# TEST-MODULE-V2.net
KiCad netlist of a schematic drawn in Altium Designer
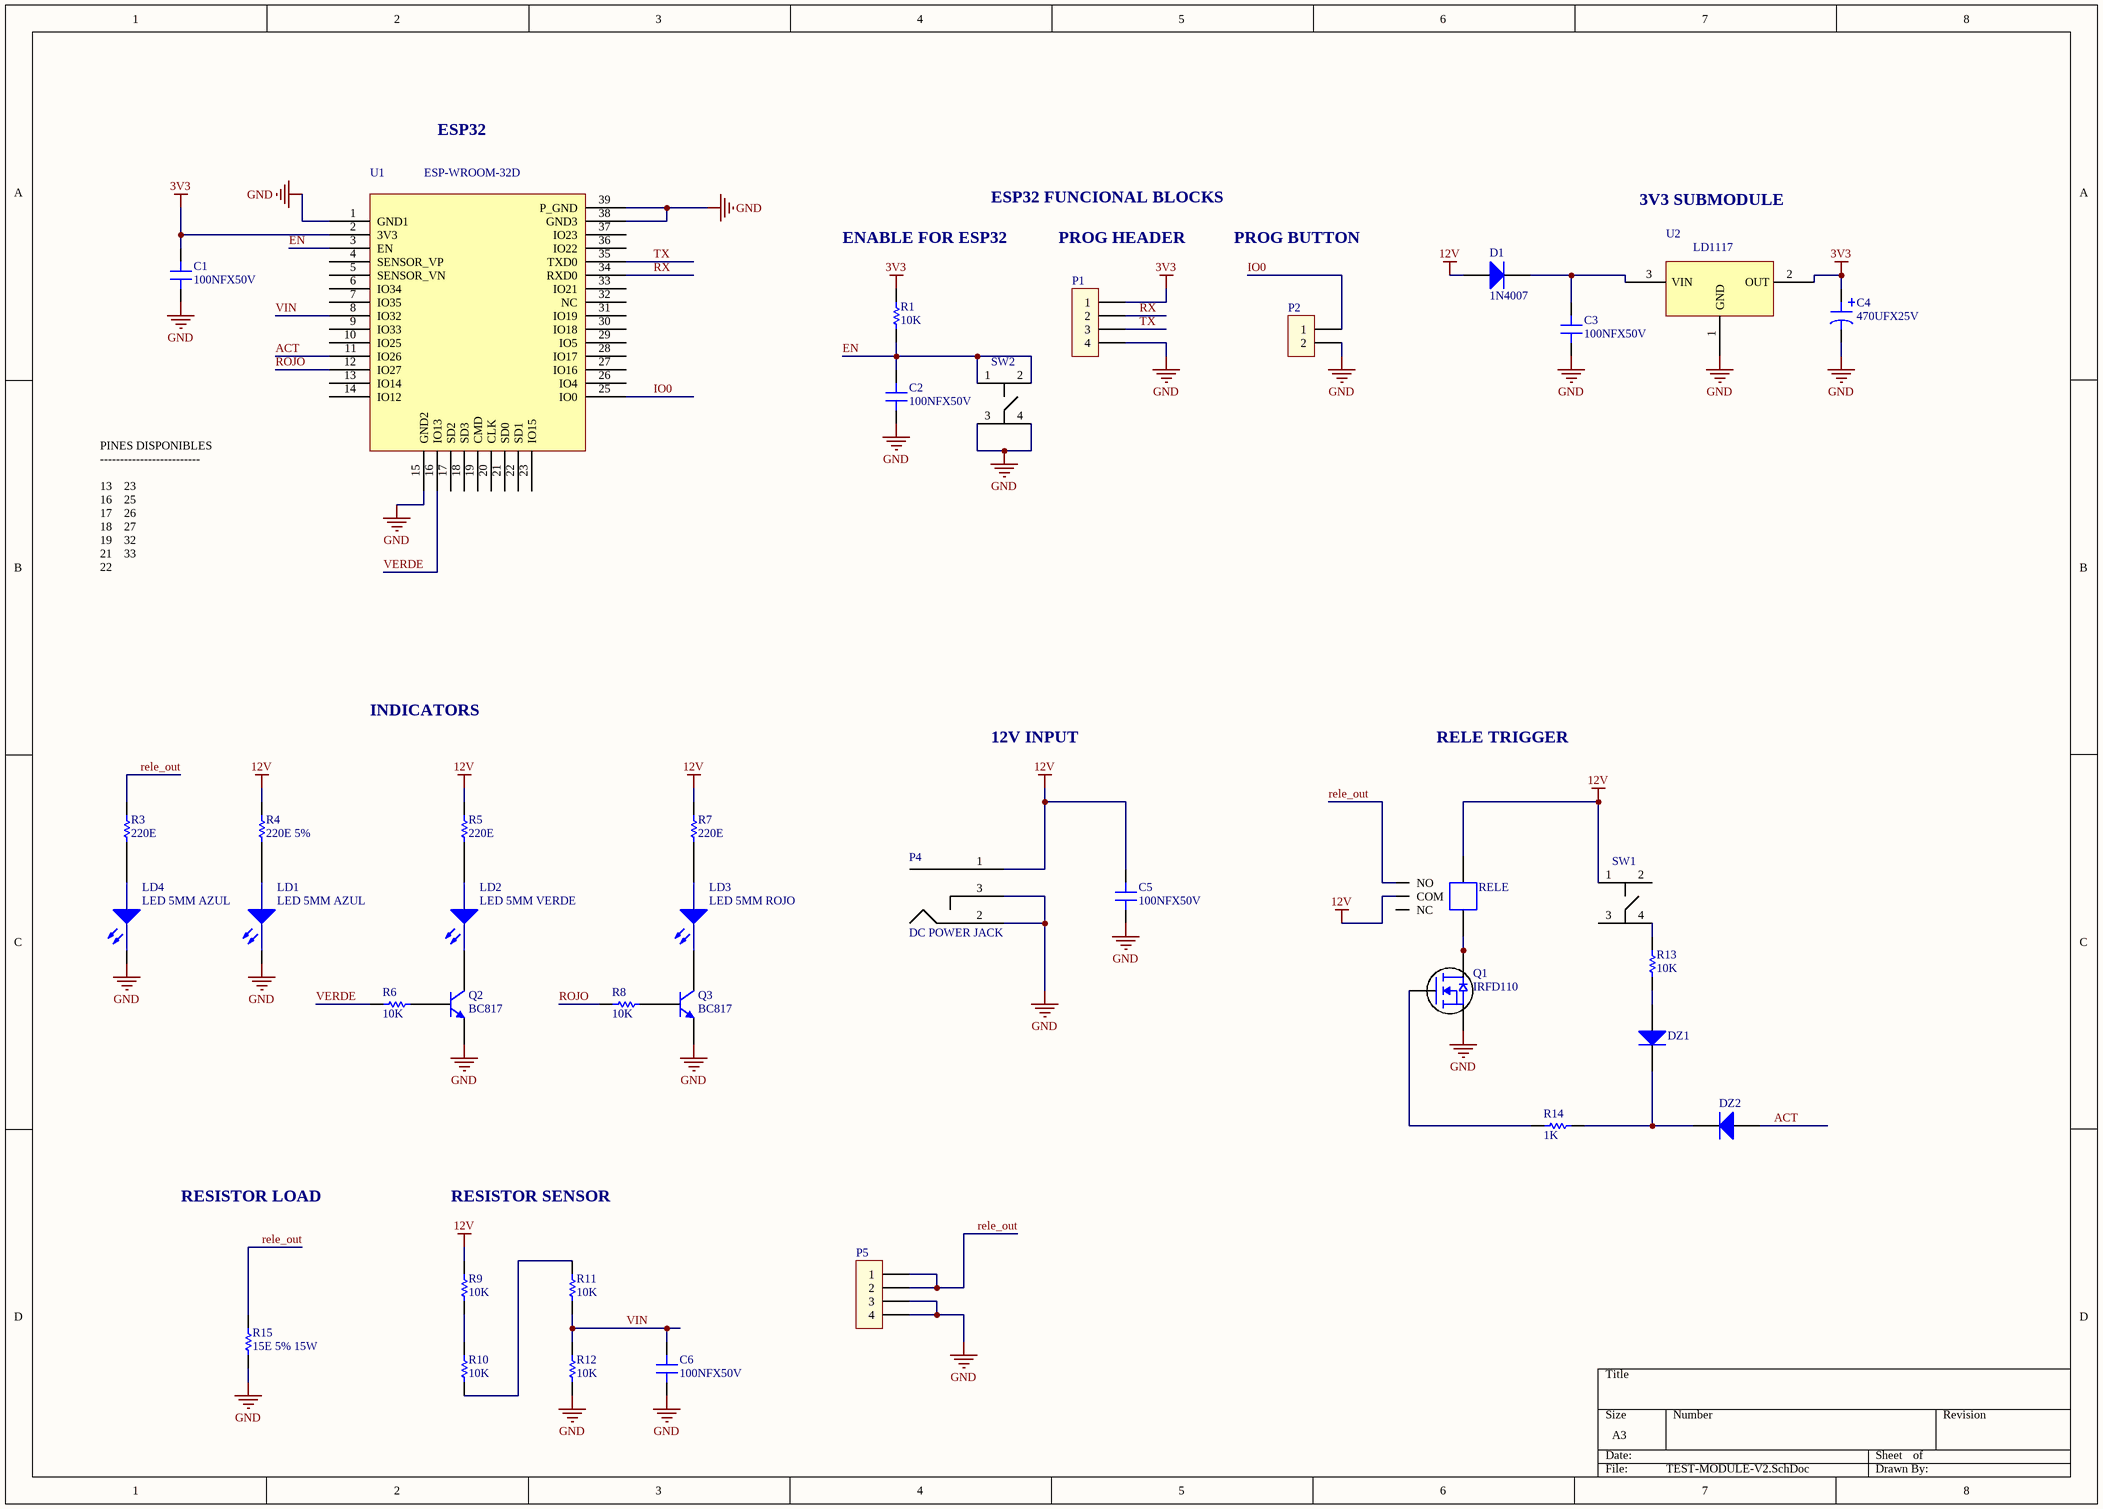
[diagram p0: TEST-MODULE-V2.SchDoc]

(export (version "E")
  (design (tool "Eeschema 10.0.6"))
  (components
    (comp (ref "C1")
      (value "100NFX50V")
      (footprint "CAP.SMD.0805")
      (description "100NFX50V X7R 10% CER.MULT. SMD 0805")
      (libsource (lib "Libreria-Capacitores") (part "Capacitor 100NFX50V X7R 10% CER.MULT. SMD 0805"))
    )
    (comp (ref "C2")
      (value "100NFX50V")
      (footprint "CAP.SMD.0805")
      (description "100NFX50V X7R 10% CER.MULT. SMD 0805")
      (libsource (lib "Libreria-Capacitores") (part "Capacitor 100NFX50V X7R 10% CER.MULT. SMD 0805"))
    )
    (comp (ref "C3")
      (value "100NFX50V")
      (footprint "CAP.SMD.0805")
      (description "100NFX50V X7R 10% CER.MULT. SMD 0805")
      (libsource (lib "Libreria-Capacitores") (part "Capacitor 100NFX50V X7R 10% CER.MULT. SMD 0805"))
    )
    (comp (ref "C4")
      (value "470UFX25V")
      (footprint "CAP-ELEC-10X13")
      (description "470UFX25V 85°C 10x13 ELE.RAD")
      (libsource (lib "Libreria-Capacitores") (part "Capacitor Electrolitico 470UFX25V 85°C 10x13 ELE.RAD"))
    )
    (comp (ref "C5")
      (value "100NFX50V")
      (footprint "CAP.SMD.0805")
      (description "100NFX50V X7R 10% CER.MULT. SMD 0805")
      (libsource (lib "Libreria-Capacitores") (part "Capacitor 100NFX50V X7R 10% CER.MULT. SMD 0805"))
    )
    (comp (ref "C6")
      (value "100NFX50V")
      (footprint "CAP.SMD.0805")
      (description "100NFX50V X7R 10% CER.MULT. SMD 0805")
      (libsource (lib "Libreria-Capacitores") (part "Capacitor 100NFX50V X7R 10% CER.MULT. SMD 0805"))
    )
    (comp (ref "D1")
      (value "1N4007")
      (footprint "Diode DO41")
      (description "Diodo 1N4007 DIODO 1A 1000V DO41")
      (libsource (lib "Libreria-Diodos") (part "Diodo 1N4007 DIODO 1A 1000V DO41"))
    )
    (comp (ref "DZ1")
      (value "M7 DIODO 1A 1000V SMD-SMA (1N4007) XYG")
      (footprint "Diode-SMD-SMA")
      (libsource (lib "Libreria-Diodos") (part "Diodo M7 DIODO 1A 1000V SMD-SMA (1N4007) XYG"))
    )
    (comp (ref "DZ2")
      (value "M7 DIODO 1A 1000V SMD-SMA (1N4007) XYG")
      (footprint "Diode-SMD-SMA")
      (libsource (lib "Libreria-Diodos") (part "Diodo M7 DIODO 1A 1000V SMD-SMA (1N4007) XYG"))
    )
    (comp (ref "LD1")
      (value "LED 5MM AZUL")
      (footprint "LED-5MM-ALTO-9-AZUL")
      (description "LED 5MM AZUL ALTO 9")
      (libsource (lib "Libreria-LEDs") (part "LED 5MM AZUL ALTO 9"))
    )
    (comp (ref "LD2")
      (value "LED 5MM VERDE")
      (footprint "LED-5MM-ALTO-9-VERDE")
      (description "LED 5MM VERDE ALTO 9")
      (libsource (lib "Libreria-LEDs") (part "LED 5MM VERDE ALTO 9"))
    )
    (comp (ref "LD3")
      (value "LED 5MM ROJO")
      (footprint "LED-5MM-ALTO-9-ROJO")
      (description "LED 5MM ROJO ALTO 9")
      (libsource (lib "Libreria-LEDs") (part "LED 5MM ROJO ALTO 9"))
    )
    (comp (ref "LD4")
      (value "LED 5MM AZUL")
      (footprint "LED-5MM-ALTO-9-AZUL")
      (description "LED 5MM AZUL ALTO 9")
      (libsource (lib "Libreria-LEDs") (part "LED 5MM AZUL ALTO 9"))
    )
    (comp (ref "P1")
      (value "IDC-HE-THT-1X4-P2.54MM")
      (footprint "IDC-HE-THT-1X4-P2.54MM")
      (libsource (lib "Libreria-Conectores") (part "IDC-HE-THT-1X4-P2.54MM"))
    )
    (comp (ref "P2")
      (value "IDC-MA-THT-1X2-P2.54MM-L11")
      (footprint "IDC-MA-THT-1X2-P2.54MM-L11")
      (libsource (lib "Libreria-Conectores") (part "IDC-MA-THT-1X2-P2.54MM-L11"))
    )
    (comp (ref "P4")
      (value "DC POWER JACK")
      (footprint "VAR-DC-JACK - VERT")
      (description "DC POWER JACK VERTICAL 2MM")
      (libsource (lib "Libreria-Varios") (part "DC POWER JACK VERTICAL 2MM"))
    )
    (comp (ref "P5")
      (value "IDC-HE-THT-1X4-P2.54MM")
      (footprint "IDC-HE-THT-1X4-P2.54MM")
      (libsource (lib "Libreria-Conectores") (part "IDC-HE-THT-1X4-P2.54MM"))
    )
    (comp (ref "Q1")
      (value "IRFD110")
      (footprint "TRA-IRFD110")
      (description "Transistor MOSFET N IRFD110")
      (libsource (lib "Libreria-Transistores") (part "Transistor MOSFET N IRFD110"))
    )
    (comp (ref "Q2")
      (value "BC817")
      (footprint "NPN.SMD.SOT23")
      (description "BC817-40 TRA.NPN 45V0.5A 0.25W SOT23")
      (libsource (lib "Libreria-Transistores") (part "Transistor BC817-40 TRA.NPN 45V0.5A 0.25W SOT23"))
    )
    (comp (ref "Q3")
      (value "BC817")
      (footprint "NPN.SMD.SOT23")
      (description "BC817-40 TRA.NPN 45V0.5A 0.25W SOT23")
      (libsource (lib "Libreria-Transistores") (part "Transistor BC817-40 TRA.NPN 45V0.5A 0.25W SOT23"))
    )
    (comp (ref "R1")
      (value "10K")
      (footprint "RES.SMD.103")
      (description "10K 5% 0805 1/8W RES.SMD")
      (libsource (lib "Libreria-Resistencias") (part "Resistencia 10K 5% 0805 1/8W"))
    )
    (comp (ref "R3")
      (value "220E")
      (footprint "RES.SMD.221")
      (description "220E 5% 0805 1/8W RES.SMD")
      (libsource (lib "Libreria-Resistencias") (part "Resistencia 220E 5% 0805 1/8W"))
    )
    (comp (ref "R4")
      (value "220E 5%")
      (footprint "RES.SMD.221")
      (description "220E 5% 0805 1/8W RES.SMD")
      (libsource (lib "Libreria-Resistencias") (part "Resistencia 220E 5% 0805 1/8W"))
    )
    (comp (ref "R5")
      (value "220E")
      (footprint "RES.SMD.221")
      (description "220E 5% 0805 1/8W RES.SMD")
      (libsource (lib "Libreria-Resistencias") (part "Resistencia 220E 5% 0805 1/8W"))
    )
    (comp (ref "R6")
      (value "10K")
      (footprint "RES.SMD.103")
      (description "10K 5% 0805 1/8W RES.SMD")
      (libsource (lib "Libreria-Resistencias") (part "Resistencia 10K 5% 0805 1/8W"))
    )
    (comp (ref "R7")
      (value "220E")
      (footprint "RES.SMD.221")
      (description "220E 5% 0805 1/8W RES.SMD")
      (libsource (lib "Libreria-Resistencias") (part "Resistencia 220E 5% 0805 1/8W"))
    )
    (comp (ref "R8")
      (value "10K")
      (footprint "RES.SMD.103")
      (description "10K 5% 0805 1/8W RES.SMD")
      (libsource (lib "Libreria-Resistencias") (part "Resistencia 10K 5% 0805 1/8W"))
    )
    (comp (ref "R9")
      (value "10K")
      (footprint "RES.SMD.103")
      (description "10K 5% 0805 1/8W RES.SMD")
      (libsource (lib "Libreria-Resistencias") (part "Resistencia 10K 5% 0805 1/8W"))
    )
    (comp (ref "R10")
      (value "10K")
      (footprint "RES.SMD.103")
      (description "10K 5% 0805 1/8W RES.SMD")
      (libsource (lib "Libreria-Resistencias") (part "Resistencia 10K 5% 0805 1/8W"))
    )
    (comp (ref "R11")
      (value "10K")
      (footprint "RES.SMD.103")
      (description "10K 5% 0805 1/8W RES.SMD")
      (libsource (lib "Libreria-Resistencias") (part "Resistencia 10K 5% 0805 1/8W"))
    )
    (comp (ref "R12")
      (value "10K")
      (footprint "RES.SMD.103")
      (description "10K 5% 0805 1/8W RES.SMD")
      (libsource (lib "Libreria-Resistencias") (part "Resistencia 10K 5% 0805 1/8W"))
    )
    (comp (ref "R13")
      (value "10K")
      (footprint "RES.SMD.103")
      (description "10K 5% 0805 1/8W RES.SMD")
      (libsource (lib "Libreria-Resistencias") (part "Resistencia 10K 5% 0805 1/8W"))
    )
    (comp (ref "R14")
      (value "1K")
      (footprint "RES.SMD.102")
      (description "1K 5% 0805 1/8W RES.SMD")
      (libsource (lib "Libreria-Resistencias") (part "Resistencia 1K 5% 0805 1/8W"))
    )
    (comp (ref "R15")
      (value "15E 5% 15W")
      (footprint "RES-CERAMICA-15W")
      (description "Resistencia Ceramica 15E 5% 15W SE15 RES.CEM")
      (libsource (lib "Libreria-Resistencias") (part "Resistencia Ceramica 15E 5% 15W SE15 RES.CEM"))
    )
    (comp (ref "RELE")
      (value "Relay simple inversor 5V 10A")
      (footprint "VAR-RELE-5V10A")
      (libsource (lib "Libreria-Varios") (part "VAR-RELE-5V Relay simple inversor 5V 10A"))
    )
    (comp (ref "SW1")
      (value "TACT-SWITCH-THT-4C-06X06(13MM)-JIANFU")
      (footprint "TACT-SWITCH-THT-4C-06X06-13MM")
      (libsource (lib "Libreria-Switches") (part "TACT-SWITCH-THT-4C-06X06(13MM)-JIANFU"))
    )
    (comp (ref "SW2")
      (value "TACT-SWITCH-THT-4C-06X06(5MM)")
      (footprint "TACT-SWITCH-THT-4C-06X06-5MM")
      (libsource (lib "Libreria-Switches") (part "TACT-SWITCH-THT-4C-06X06(5MM)"))
    )
    (comp (ref "U1")
      (value "ESP32-WROOM-32D")
      (footprint "ESP32-WROOM-32D")
      (libsource (lib "Libreria-Semiconductores") (part "ESP32-WROOM-32D"))
    )
    (comp (ref "U2")
      (value "LD1117S33TR SMD SOT-223-3 0.8A 3.3V LDO LINEAR REGULATOR")
      (footprint "SOT223-3")
      (libsource (lib "Libreria-Semiconductores") (part "LD1117S33TR SMD SOT-223-3 0.8A 3.3V LDO LINEAR REGULATOR"))
    )
  )
  (nets
    (net (code "1") (name "/ACT") (class "Default")
      (node (ref "DZ2") (pin "A") (pinfunction "A_A") (pintype "passive"))
      (node (ref "U1") (pin "11") (pinfunction "IO26_11") (pintype "passive"))
    )
    (net (code "2") (name "/EN") (class "Default")
      (node (ref "C2") (pin "2") (pinfunction "2_2") (pintype "passive"))
      (node (ref "R1") (pin "1") (pinfunction "1_1") (pintype "passive"))
      (node (ref "SW2") (pin "1") (pinfunction "1_1") (pintype "passive"))
      (node (ref "SW2") (pin "2") (pinfunction "2_2") (pintype "passive"))
      (node (ref "U1") (pin "3") (pinfunction "EN_3") (pintype "passive"))
    )
    (net (code "3") (name "/IO0") (class "Default")
      (node (ref "P2") (pin "1") (pinfunction "1_1") (pintype "passive"))
      (node (ref "U1") (pin "25") (pinfunction "IO0_25") (pintype "passive"))
    )
    (net (code "4") (name "/ROJO") (class "Default")
      (node (ref "R8") (pin "2") (pinfunction "2_2") (pintype "passive"))
      (node (ref "U1") (pin "12") (pinfunction "IO27_12") (pintype "passive"))
    )
    (net (code "5") (name "/RX") (class "Default")
      (node (ref "P1") (pin "2") (pinfunction "2_2") (pintype "passive"))
      (node (ref "U1") (pin "34") (pinfunction "RXD0_34") (pintype "passive"))
    )
    (net (code "6") (name "/TX") (class "Default")
      (node (ref "P1") (pin "3") (pinfunction "3_3") (pintype "passive"))
      (node (ref "U1") (pin "35") (pinfunction "TXD0_35") (pintype "passive"))
    )
    (net (code "7") (name "/VERDE") (class "Default")
      (node (ref "R6") (pin "1") (pinfunction "1_1") (pintype "passive"))
      (node (ref "U1") (pin "16") (pinfunction "IO13_16") (pintype "passive"))
    )
    (net (code "8") (name "/VIN") (class "Default")
      (node (ref "C6") (pin "2") (pinfunction "2_2") (pintype "passive"))
      (node (ref "R11") (pin "1") (pinfunction "1_1") (pintype "passive"))
      (node (ref "R12") (pin "2") (pinfunction "2_2") (pintype "passive"))
      (node (ref "U1") (pin "8") (pinfunction "IO32_8") (pintype "passive"))
    )
    (net (code "9") (name "/rele_out") (class "Default")
      (node (ref "P5") (pin "1") (pinfunction "1_1") (pintype "passive"))
      (node (ref "P5") (pin "2") (pinfunction "2_2") (pintype "passive"))
      (node (ref "R15") (pin "2") (pinfunction "2_2") (pintype "passive"))
      (node (ref "R3") (pin "2") (pinfunction "2_2") (pintype "passive"))
      (node (ref "RELE") (pin "4") (pinfunction "NO_4") (pintype "passive"))
    )
    (net (code "10") (name "3V3") (class "Default")
      (node (ref "C1") (pin "2") (pinfunction "2_2") (pintype "passive"))
      (node (ref "C4") (pin "1") (pinfunction "1_1") (pintype "passive"))
      (node (ref "P1") (pin "1") (pinfunction "1_1") (pintype "passive"))
      (node (ref "R1") (pin "2") (pinfunction "2_2") (pintype "passive"))
      (node (ref "U1") (pin "2") (pinfunction "3V3_2") (pintype "passive"))
      (node (ref "U2") (pin "2") (pinfunction "OUT_2") (pintype "passive"))
    )
    (net (code "11") (name "12V") (class "Default")
      (node (ref "C5") (pin "2") (pinfunction "2_2") (pintype "passive"))
      (node (ref "D1") (pin "A") (pinfunction "A_A") (pintype "passive"))
      (node (ref "P4") (pin "1") (pinfunction "1_1") (pintype "passive"))
      (node (ref "R4") (pin "2") (pinfunction "2_2") (pintype "passive"))
      (node (ref "R5") (pin "2") (pinfunction "2_2") (pintype "passive"))
      (node (ref "R7") (pin "2") (pinfunction "2_2") (pintype "passive"))
      (node (ref "R9") (pin "2") (pinfunction "2_2") (pintype "passive"))
      (node (ref "RELE") (pin "2") (pinfunction "2_2") (pintype "passive"))
      (node (ref "RELE") (pin "3") (pinfunction "COM_3") (pintype "passive"))
      (node (ref "SW1") (pin "1") (pinfunction "1_1") (pintype "passive"))
    )
    (net (code "12") (name "GND") (class "Default")
      (node (ref "C1") (pin "1") (pinfunction "1_1") (pintype "passive"))
      (node (ref "C2") (pin "1") (pinfunction "1_1") (pintype "passive"))
      (node (ref "C3") (pin "1") (pinfunction "1_1") (pintype "passive"))
      (node (ref "C4") (pin "2") (pinfunction "2_2") (pintype "passive"))
      (node (ref "C5") (pin "1") (pinfunction "1_1") (pintype "passive"))
      (node (ref "C6") (pin "1") (pinfunction "1_1") (pintype "passive"))
      (node (ref "LD1") (pin "K") (pinfunction "KB_K") (pintype "passive"))
      (node (ref "LD4") (pin "K") (pinfunction "KB_K") (pintype "passive"))
      (node (ref "P1") (pin "4") (pinfunction "4_4") (pintype "passive"))
      (node (ref "P2") (pin "2") (pinfunction "2_2") (pintype "passive"))
      (node (ref "P4") (pin "2") (pinfunction "2_2") (pintype "passive"))
      (node (ref "P4") (pin "3") (pinfunction "3_3") (pintype "passive"))
      (node (ref "P5") (pin "3") (pinfunction "3_3") (pintype "passive"))
      (node (ref "P5") (pin "4") (pinfunction "4_4") (pintype "passive"))
      (node (ref "Q1") (pin "4") (pinfunction "4_4") (pintype "passive"))
      (node (ref "Q2") (pin "2") (pinfunction "E_2") (pintype "passive"))
      (node (ref "Q3") (pin "2") (pinfunction "E_2") (pintype "passive"))
      (node (ref "R12") (pin "1") (pinfunction "1_1") (pintype "passive"))
      (node (ref "R15") (pin "1") (pinfunction "1_1") (pintype "passive"))
      (node (ref "SW2") (pin "3") (pinfunction "3_3") (pintype "passive"))
      (node (ref "SW2") (pin "4") (pinfunction "4_4") (pintype "passive"))
      (node (ref "U1") (pin "1") (pinfunction "GND1_1") (pintype "passive"))
      (node (ref "U1") (pin "15") (pinfunction "GND2_15") (pintype "passive"))
      (node (ref "U1") (pin "38") (pinfunction "GND3_38") (pintype "passive"))
      (node (ref "U1") (pin "39") (pinfunction "P_GND_39") (pintype "passive"))
      (node (ref "U2") (pin "1") (pinfunction "GND_1") (pintype "passive"))
    )
    (net (code "13") (name "Net-(DZ1-PadA)") (class "Default")
      (node (ref "DZ1") (pin "A") (pinfunction "A_A") (pintype "passive"))
      (node (ref "R13") (pin "1") (pinfunction "1_1") (pintype "passive"))
    )
    (net (code "14") (name "Net-(DZ1-PadK)") (class "Default")
      (node (ref "DZ1") (pin "K") (pinfunction "K_K") (pintype "passive"))
      (node (ref "DZ2") (pin "K") (pinfunction "K_K") (pintype "passive"))
      (node (ref "R14") (pin "2") (pinfunction "2_2") (pintype "passive"))
    )
    (net (code "15") (name "Net-(LD1-AB)") (class "Default")
      (node (ref "LD1") (pin "A") (pinfunction "AB_A") (pintype "passive"))
      (node (ref "R4") (pin "1") (pinfunction "1_1") (pintype "passive"))
    )
    (net (code "16") (name "Net-(LD2-AB)") (class "Default")
      (node (ref "LD2") (pin "A") (pinfunction "AB_A") (pintype "passive"))
      (node (ref "R5") (pin "1") (pinfunction "1_1") (pintype "passive"))
    )
    (net (code "17") (name "Net-(LD2-KB)") (class "Default")
      (node (ref "LD2") (pin "K") (pinfunction "KB_K") (pintype "passive"))
      (node (ref "Q2") (pin "3") (pinfunction "C_3") (pintype "passive"))
    )
    (net (code "18") (name "Net-(LD3-AB)") (class "Default")
      (node (ref "LD3") (pin "A") (pinfunction "AB_A") (pintype "passive"))
      (node (ref "R7") (pin "1") (pinfunction "1_1") (pintype "passive"))
    )
    (net (code "19") (name "Net-(LD3-KB)") (class "Default")
      (node (ref "LD3") (pin "K") (pinfunction "KB_K") (pintype "passive"))
      (node (ref "Q3") (pin "3") (pinfunction "C_3") (pintype "passive"))
    )
    (net (code "20") (name "Net-(LD4-AB)") (class "Default")
      (node (ref "LD4") (pin "A") (pinfunction "AB_A") (pintype "passive"))
      (node (ref "R3") (pin "1") (pinfunction "1_1") (pintype "passive"))
    )
    (net (code "21") (name "Net-(Q1-Pad1)") (class "Default")
      (node (ref "Q1") (pin "1") (pinfunction "1_1") (pintype "passive"))
      (node (ref "Q1") (pin "2") (pinfunction "2_2") (pintype "passive"))
      (node (ref "RELE") (pin "1") (pinfunction "1_1") (pintype "passive"))
    )
    (net (code "22") (name "Net-(Q1-Pad3)") (class "Default")
      (node (ref "Q1") (pin "3") (pinfunction "3_3") (pintype "passive"))
      (node (ref "R14") (pin "1") (pinfunction "1_1") (pintype "passive"))
    )
    (net (code "23") (name "Net-(Q2-B)") (class "Default")
      (node (ref "Q2") (pin "1") (pinfunction "B_1") (pintype "passive"))
      (node (ref "R6") (pin "2") (pinfunction "2_2") (pintype "passive"))
    )
    (net (code "24") (name "Net-(Q3-B)") (class "Default")
      (node (ref "Q3") (pin "1") (pinfunction "B_1") (pintype "passive"))
      (node (ref "R8") (pin "1") (pinfunction "1_1") (pintype "passive"))
    )
    (net (code "25") (name "Net-(R10-Pad1)") (class "Default")
      (node (ref "R10") (pin "1") (pinfunction "1_1") (pintype "passive"))
      (node (ref "R11") (pin "2") (pinfunction "2_2") (pintype "passive"))
    )
    (net (code "26") (name "Net-(R10-Pad2)") (class "Default")
      (node (ref "R10") (pin "2") (pinfunction "2_2") (pintype "passive"))
      (node (ref "R9") (pin "1") (pinfunction "1_1") (pintype "passive"))
    )
    (net (code "27") (name "Net-(R13-Pad2)") (class "Default")
      (node (ref "R13") (pin "2") (pinfunction "2_2") (pintype "passive"))
      (node (ref "SW1") (pin "4") (pinfunction "4_4") (pintype "passive"))
    )
    (net (code "28") (name "Net-(U2-VIN)") (class "Default")
      (node (ref "C3") (pin "2") (pinfunction "2_2") (pintype "passive"))
      (node (ref "D1") (pin "K") (pinfunction "K_K") (pintype "passive"))
      (node (ref "U2") (pin "3") (pinfunction "VIN_3") (pintype "passive"))
    )
    (net (code "29") (name "unconnected-(RELE-NC-Pad5)") (class "Default")
      (node (ref "RELE") (pin "5") (pinfunction "NC_5") (pintype "passive"))
    )
    (net (code "30") (name "unconnected-(SW1-Pad2)") (class "Default")
      (node (ref "SW1") (pin "2") (pinfunction "2_2") (pintype "passive"))
    )
    (net (code "31") (name "unconnected-(SW1-Pad3)") (class "Default")
      (node (ref "SW1") (pin "3") (pinfunction "3_3") (pintype "passive"))
    )
    (net (code "32") (name "unconnected-(U1-CLK-Pad20)") (class "Default")
      (node (ref "U1") (pin "20") (pinfunction "CLK_20") (pintype "passive"))
    )
    (net (code "33") (name "unconnected-(U1-CMD-Pad19)") (class "Default")
      (node (ref "U1") (pin "19") (pinfunction "CMD_19") (pintype "passive"))
    )
    (net (code "34") (name "unconnected-(U1-IO4-Pad26)") (class "Default")
      (node (ref "U1") (pin "26") (pinfunction "IO4_26") (pintype "passive"))
    )
    (net (code "35") (name "unconnected-(U1-IO5-Pad29)") (class "Default")
      (node (ref "U1") (pin "29") (pinfunction "IO5_29") (pintype "passive"))
    )
    (net (code "36") (name "unconnected-(U1-IO12-Pad14)") (class "Default")
      (node (ref "U1") (pin "14") (pinfunction "IO12_14") (pintype "passive"))
    )
    (net (code "37") (name "unconnected-(U1-IO14-Pad13)") (class "Default")
      (node (ref "U1") (pin "13") (pinfunction "IO14_13") (pintype "passive"))
    )
    (net (code "38") (name "unconnected-(U1-IO15-Pad23)") (class "Default")
      (node (ref "U1") (pin "23") (pinfunction "IO15_23") (pintype "passive"))
    )
    (net (code "39") (name "unconnected-(U1-IO16-Pad27)") (class "Default")
      (node (ref "U1") (pin "27") (pinfunction "IO16_27") (pintype "passive"))
    )
    (net (code "40") (name "unconnected-(U1-IO17-Pad28)") (class "Default")
      (node (ref "U1") (pin "28") (pinfunction "IO17_28") (pintype "passive"))
    )
    (net (code "41") (name "unconnected-(U1-IO18-Pad30)") (class "Default")
      (node (ref "U1") (pin "30") (pinfunction "IO18_30") (pintype "passive"))
    )
    (net (code "42") (name "unconnected-(U1-IO19-Pad31)") (class "Default")
      (node (ref "U1") (pin "31") (pinfunction "IO19_31") (pintype "passive"))
    )
    (net (code "43") (name "unconnected-(U1-IO21-Pad33)") (class "Default")
      (node (ref "U1") (pin "33") (pinfunction "IO21_33") (pintype "passive"))
    )
    (net (code "44") (name "unconnected-(U1-IO22-Pad36)") (class "Default")
      (node (ref "U1") (pin "36") (pinfunction "IO22_36") (pintype "passive"))
    )
    (net (code "45") (name "unconnected-(U1-IO23-Pad37)") (class "Default")
      (node (ref "U1") (pin "37") (pinfunction "IO23_37") (pintype "passive"))
    )
    (net (code "46") (name "unconnected-(U1-IO25-Pad10)") (class "Default")
      (node (ref "U1") (pin "10") (pinfunction "IO25_10") (pintype "passive"))
    )
    (net (code "47") (name "unconnected-(U1-IO33-Pad9)") (class "Default")
      (node (ref "U1") (pin "9") (pinfunction "IO33_9") (pintype "passive"))
    )
    (net (code "48") (name "unconnected-(U1-IO34-Pad6)") (class "Default")
      (node (ref "U1") (pin "6") (pinfunction "IO34_6") (pintype "passive"))
    )
    (net (code "49") (name "unconnected-(U1-IO35-Pad7)") (class "Default")
      (node (ref "U1") (pin "7") (pinfunction "IO35_7") (pintype "passive"))
    )
    (net (code "50") (name "unconnected-(U1-NC-Pad32)") (class "Default")
      (node (ref "U1") (pin "32") (pinfunction "NC_32") (pintype "passive"))
    )
    (net (code "51") (name "unconnected-(U1-SD0-Pad21)") (class "Default")
      (node (ref "U1") (pin "21") (pinfunction "SD0_21") (pintype "passive"))
    )
    (net (code "52") (name "unconnected-(U1-SD1-Pad22)") (class "Default")
      (node (ref "U1") (pin "22") (pinfunction "SD1_22") (pintype "passive"))
    )
    (net (code "53") (name "unconnected-(U1-SD2-Pad17)") (class "Default")
      (node (ref "U1") (pin "17") (pinfunction "SD2_17") (pintype "passive"))
    )
    (net (code "54") (name "unconnected-(U1-SD3-Pad18)") (class "Default")
      (node (ref "U1") (pin "18") (pinfunction "SD3_18") (pintype "passive"))
    )
    (net (code "55") (name "unconnected-(U1-SENSOR_VN-Pad5)") (class "Default")
      (node (ref "U1") (pin "5") (pinfunction "SENSOR_VN_5") (pintype "passive"))
    )
    (net (code "56") (name "unconnected-(U1-SENSOR_VP-Pad4)") (class "Default")
      (node (ref "U1") (pin "4") (pinfunction "SENSOR_VP_4") (pintype "passive"))
    )
  )
)
